# ZULU-T868-TX-Prototype.net
KiCad netlist of a schematic drawn in EAGLE
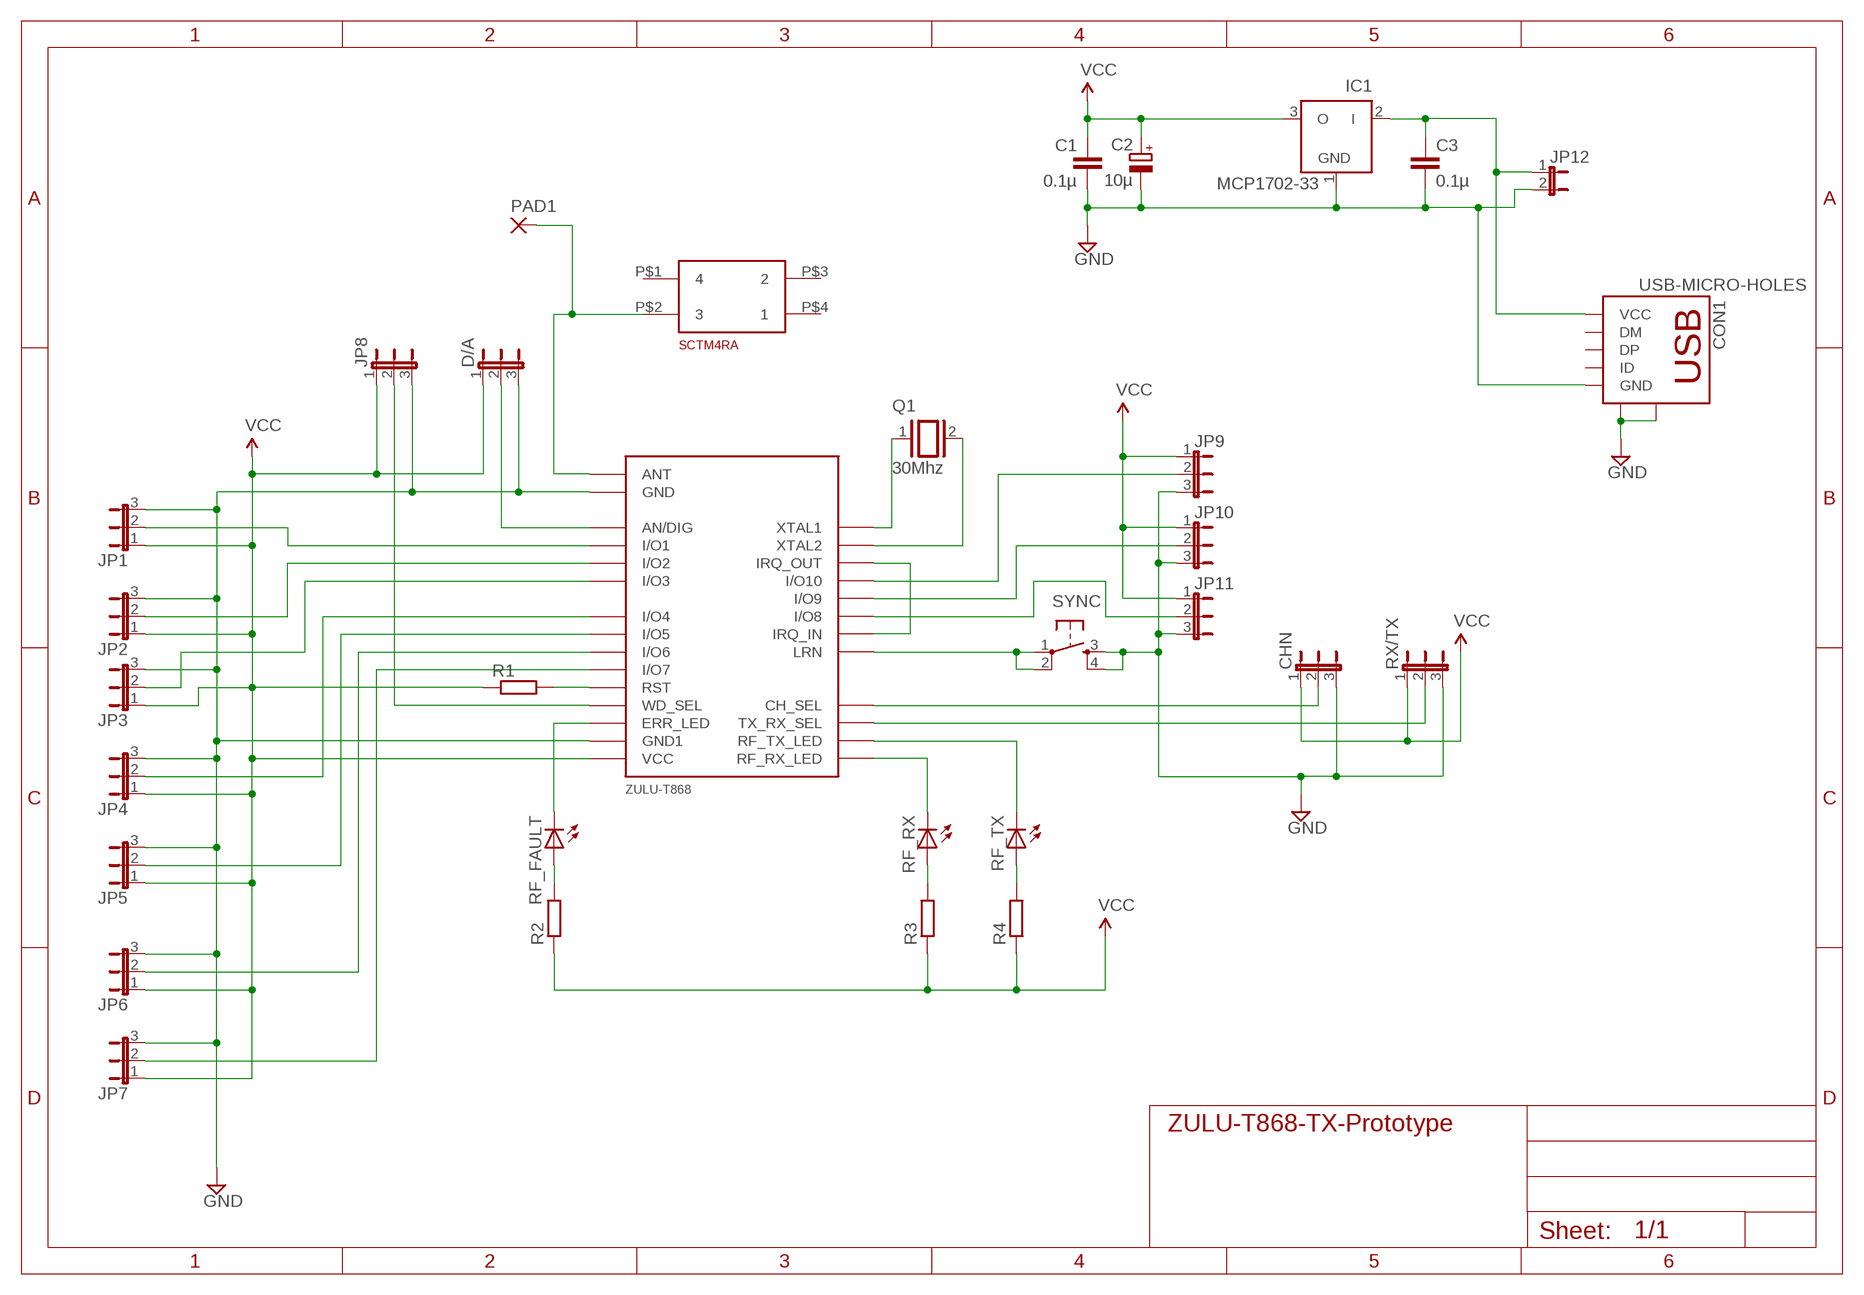
[diagram p0: schematic, sheet 1]

(export (version "E")
  (design (tool "Eeschema 10.0.6"))
  (components
    (comp (ref "C1")
      (value "0.1µ")
      (footprint "eagle-import:C0805")
      (libsource (lib "eagle-import") (part "C-EUC0805"))
    )
    (comp (ref "C2")
      (value "10µ")
      (footprint "eagle-import:E1,8-4")
      (libsource (lib "eagle-import") (part "CPOL-EUE1.8-4"))
    )
    (comp (ref "C3")
      (value "0.1µ")
      (footprint "eagle-import:C0805")
      (libsource (lib "eagle-import") (part "C-EUC0805"))
    )
    (comp (ref "CHN")
      (value "JP2E")
      (footprint "eagle-import:JP2")
      (libsource (lib "eagle-import") (part "JP2E"))
    )
    (comp (ref "CON1")
      (value "USB-MICRO-HOLES")
      (footprint "eagle-import:MICRO-USB-B-HOLES")
      (libsource (lib "eagle-import") (part "USB-MICRO-HOLES"))
    )
    (comp (ref "D/A")
      (value "JP2E")
      (footprint "eagle-import:JP2")
      (libsource (lib "eagle-import") (part "JP2E"))
    )
    (comp (ref "IC1")
      (value "MCP1702-33")
      (footprint "eagle-import:TO92")
      (libsource (lib "eagle-import") (part "MCP1702Z"))
    )
    (comp (ref "JP1")
      (value "JP2E")
      (footprint "eagle-import:JP2")
      (libsource (lib "eagle-import") (part "JP2E"))
    )
    (comp (ref "JP2")
      (value "JP2E")
      (footprint "eagle-import:JP2")
      (libsource (lib "eagle-import") (part "JP2E"))
    )
    (comp (ref "JP3")
      (value "JP2E")
      (footprint "eagle-import:JP2")
      (libsource (lib "eagle-import") (part "JP2E"))
    )
    (comp (ref "JP4")
      (value "JP2E")
      (footprint "eagle-import:JP2")
      (libsource (lib "eagle-import") (part "JP2E"))
    )
    (comp (ref "JP5")
      (value "JP2E")
      (footprint "eagle-import:JP2")
      (libsource (lib "eagle-import") (part "JP2E"))
    )
    (comp (ref "JP6")
      (value "JP2E")
      (footprint "eagle-import:JP2")
      (libsource (lib "eagle-import") (part "JP2E"))
    )
    (comp (ref "JP7")
      (value "JP2E")
      (footprint "eagle-import:JP2")
      (libsource (lib "eagle-import") (part "JP2E"))
    )
    (comp (ref "JP8")
      (value "JP2E")
      (footprint "eagle-import:JP2")
      (libsource (lib "eagle-import") (part "JP2E"))
    )
    (comp (ref "JP9")
      (value "JP2E")
      (footprint "eagle-import:JP2")
      (libsource (lib "eagle-import") (part "JP2E"))
    )
    (comp (ref "JP10")
      (value "JP2E")
      (footprint "eagle-import:JP2")
      (libsource (lib "eagle-import") (part "JP2E"))
    )
    (comp (ref "JP11")
      (value "JP2E")
      (footprint "eagle-import:JP2")
      (libsource (lib "eagle-import") (part "JP2E"))
    )
    (comp (ref "JP12")
      (value "JP1E")
      (footprint "eagle-import:JP1")
      (libsource (lib "eagle-import") (part "JP1E"))
    )
    (comp (ref "PAD1")
      (value "1,6/0,8")
      (footprint "eagle-import:1,6_0,8")
      (libsource (lib "eagle-import") (part "1,6/0,8"))
    )
    (comp (ref "Q1")
      (value "30Mhz")
      (footprint "eagle-import:QS")
      (libsource (lib "eagle-import") (part "XTAL/S"))
    )
    (comp (ref "R1")
      (value "R-EU_M0805")
      (footprint "eagle-import:M0805")
      (libsource (lib "eagle-import") (part "R-EU_M0805"))
    )
    (comp (ref "R2")
      (value "R-EU_M0805")
      (footprint "eagle-import:M0805")
      (libsource (lib "eagle-import") (part "R-EU_M0805"))
    )
    (comp (ref "R3")
      (value "R-EU_M0805")
      (footprint "eagle-import:M0805")
      (libsource (lib "eagle-import") (part "R-EU_M0805"))
    )
    (comp (ref "R4")
      (value "R-EU_M0805")
      (footprint "eagle-import:M0805")
      (libsource (lib "eagle-import") (part "R-EU_M0805"))
    )
    (comp (ref "RF_FAULT")
      (value "LEDCHIPLED_0805")
      (footprint "eagle-import:CHIPLED_0805")
      (libsource (lib "eagle-import") (part "LEDCHIPLED_0805"))
    )
    (comp (ref "RF_RX")
      (value "LEDCHIPLED_0805")
      (footprint "eagle-import:CHIPLED_0805")
      (libsource (lib "eagle-import") (part "LEDCHIPLED_0805"))
    )
    (comp (ref "RF_TX")
      (value "LEDCHIPLED_0805")
      (footprint "eagle-import:CHIPLED_0805")
      (libsource (lib "eagle-import") (part "LEDCHIPLED_0805"))
    )
    (comp (ref "RX/TX")
      (value "JP2E")
      (footprint "eagle-import:JP2")
      (libsource (lib "eagle-import") (part "JP2E"))
    )
    (comp (ref "SYNC")
      (value "TAC_SWITCHPTH")
      (footprint "eagle-import:TACTILE-PTH")
      (libsource (lib "eagle-import") (part "TAC_SWITCHPTH"))
    )
    (comp (ref "U$1")
      (value "SCTM4RA")
      (footprint "eagle-import:SCTM4RA")
      (libsource (lib "eagle-import") (part "SCTM4RA"))
    )
    (comp (ref "U$2")
      (value "ZULU-T868")
      (footprint "eagle-import:ZULU-T-MODULE")
      (libsource (lib "eagle-import") (part "ZULU-T868"))
    )
  )
  (nets
    (net (code "1") (name "GND") (class "Default")
      (node (ref "C1") (pin "2") (pinfunction "2_2") (pintype "passive"))
      (node (ref "C2") (pin "-") (pinfunction "-_-") (pintype "passive"))
      (node (ref "C3") (pin "2") (pinfunction "2_2") (pintype "passive"))
      (node (ref "CHN") (pin "3") (pinfunction "3_3") (pintype "passive"))
      (node (ref "CON1") (pin "P$5") (pinfunction "GND_P$5") (pintype "bidirectional"))
      (node (ref "CON1") (pin "SHIELD1") (pinfunction "SHIELD1_SHIELD1") (pintype "bidirectional"))
      (node (ref "CON1") (pin "SHIELD2") (pinfunction "SHIELD2_SHIELD2") (pintype "bidirectional"))
      (node (ref "D/A") (pin "3") (pinfunction "3_3") (pintype "passive"))
      (node (ref "IC1") (pin "1") (pinfunction "GND_1") (pintype "power_in"))
      (node (ref "JP1") (pin "3") (pinfunction "3_3") (pintype "passive"))
      (node (ref "JP10") (pin "3") (pinfunction "3_3") (pintype "passive"))
      (node (ref "JP11") (pin "3") (pinfunction "3_3") (pintype "passive"))
      (node (ref "JP12") (pin "2") (pinfunction "2_2") (pintype "passive"))
      (node (ref "JP2") (pin "3") (pinfunction "3_3") (pintype "passive"))
      (node (ref "JP3") (pin "3") (pinfunction "3_3") (pintype "passive"))
      (node (ref "JP4") (pin "3") (pinfunction "3_3") (pintype "passive"))
      (node (ref "JP5") (pin "3") (pinfunction "3_3") (pintype "passive"))
      (node (ref "JP6") (pin "3") (pinfunction "3_3") (pintype "passive"))
      (node (ref "JP7") (pin "3") (pinfunction "3_3") (pintype "passive"))
      (node (ref "JP8") (pin "3") (pinfunction "3_3") (pintype "passive"))
      (node (ref "JP9") (pin "3") (pinfunction "3_3") (pintype "passive"))
      (node (ref "RX/TX") (pin "3") (pinfunction "3_3") (pintype "passive"))
      (node (ref "SYNC") (pin "3") (pinfunction "3_3") (pintype "passive"))
      (node (ref "SYNC") (pin "4") (pinfunction "4_4") (pintype "passive"))
      (node (ref "U$2") (pin "P$15") (pinfunction "GND1_P$15") (pintype "bidirectional"))
      (node (ref "U$2") (pin "P$2") (pinfunction "GND_P$2") (pintype "bidirectional"))
    )
    (net (code "2") (name "Net-(CON1-VCC)") (class "Default")
      (node (ref "C3") (pin "1") (pinfunction "1_1") (pintype "passive"))
      (node (ref "CON1") (pin "P$1") (pinfunction "VCC_P$1") (pintype "bidirectional"))
      (node (ref "IC1") (pin "2") (pinfunction "I_2") (pintype "input"))
      (node (ref "JP12") (pin "1") (pinfunction "1_1") (pintype "passive"))
    )
    (net (code "3") (name "Net-(PAD1-P)") (class "Default")
      (node (ref "PAD1") (pin "1") (pinfunction "P_1") (pintype "passive"))
      (node (ref "U$1") (pin "P$2") (pinfunction "3_P$2") (pintype "bidirectional"))
      (node (ref "U$2") (pin "P$1") (pinfunction "ANT_P$1") (pintype "bidirectional"))
    )
    (net (code "4") (name "Net-(R2-Pad2)") (class "Default")
      (node (ref "R2") (pin "2") (pinfunction "2_2") (pintype "passive"))
      (node (ref "RF_FAULT") (pin "A") (pinfunction "A_A") (pintype "passive"))
    )
    (net (code "5") (name "Net-(R3-Pad2)") (class "Default")
      (node (ref "R3") (pin "2") (pinfunction "2_2") (pintype "passive"))
      (node (ref "RF_RX") (pin "A") (pinfunction "A_A") (pintype "passive"))
    )
    (net (code "6") (name "Net-(R4-Pad2)") (class "Default")
      (node (ref "R4") (pin "2") (pinfunction "2_2") (pintype "passive"))
      (node (ref "RF_TX") (pin "A") (pinfunction "A_A") (pintype "passive"))
    )
    (net (code "7") (name "Net-(U$2-AN{slash}DIG)") (class "Default")
      (node (ref "D/A") (pin "2") (pinfunction "2_2") (pintype "passive"))
      (node (ref "U$2") (pin "P$3") (pinfunction "AN/DIG_P$3") (pintype "bidirectional"))
    )
    (net (code "8") (name "Net-(U$2-CH_SEL)") (class "Default")
      (node (ref "CHN") (pin "2") (pinfunction "2_2") (pintype "passive"))
      (node (ref "U$2") (pin "P$20") (pinfunction "CH_SEL_P$20") (pintype "bidirectional"))
    )
    (net (code "9") (name "Net-(U$2-ERR_LED)") (class "Default")
      (node (ref "RF_FAULT") (pin "C") (pinfunction "C_C") (pintype "passive"))
      (node (ref "U$2") (pin "P$14") (pinfunction "ERR_LED_P$14") (pintype "bidirectional"))
    )
    (net (code "10") (name "Net-(U$2-IRQ_IN)") (class "Default")
      (node (ref "U$2") (pin "P$24") (pinfunction "IRQ_IN_P$24") (pintype "bidirectional"))
      (node (ref "U$2") (pin "P$28") (pinfunction "IRQ_OUT_P$28") (pintype "bidirectional"))
    )
    (net (code "11") (name "Net-(U$2-I{slash}O1)") (class "Default")
      (node (ref "JP1") (pin "2") (pinfunction "2_2") (pintype "passive"))
      (node (ref "U$2") (pin "P$4") (pinfunction "I/O1_P$4") (pintype "bidirectional"))
    )
    (net (code "12") (name "Net-(U$2-I{slash}O2)") (class "Default")
      (node (ref "JP2") (pin "2") (pinfunction "2_2") (pintype "passive"))
      (node (ref "U$2") (pin "P$5") (pinfunction "I/O2_P$5") (pintype "bidirectional"))
    )
    (net (code "13") (name "Net-(U$2-I{slash}O3)") (class "Default")
      (node (ref "JP3") (pin "2") (pinfunction "2_2") (pintype "passive"))
      (node (ref "U$2") (pin "P$6") (pinfunction "I/O3_P$6") (pintype "bidirectional"))
    )
    (net (code "14") (name "Net-(U$2-I{slash}O4)") (class "Default")
      (node (ref "JP4") (pin "2") (pinfunction "2_2") (pintype "passive"))
      (node (ref "U$2") (pin "P$8") (pinfunction "I/O4_P$8") (pintype "bidirectional"))
    )
    (net (code "15") (name "Net-(U$2-I{slash}O5)") (class "Default")
      (node (ref "JP5") (pin "2") (pinfunction "2_2") (pintype "passive"))
      (node (ref "U$2") (pin "P$9") (pinfunction "I/O5_P$9") (pintype "bidirectional"))
    )
    (net (code "16") (name "Net-(U$2-I{slash}O6)") (class "Default")
      (node (ref "JP6") (pin "2") (pinfunction "2_2") (pintype "passive"))
      (node (ref "U$2") (pin "P$10") (pinfunction "I/O6_P$10") (pintype "bidirectional"))
    )
    (net (code "17") (name "Net-(U$2-I{slash}O7)") (class "Default")
      (node (ref "JP7") (pin "2") (pinfunction "2_2") (pintype "passive"))
      (node (ref "U$2") (pin "P$11") (pinfunction "I/O7_P$11") (pintype "bidirectional"))
    )
    (net (code "18") (name "Net-(U$2-I{slash}O8)") (class "Default")
      (node (ref "JP11") (pin "2") (pinfunction "2_2") (pintype "passive"))
      (node (ref "U$2") (pin "P$25") (pinfunction "I/O8_P$25") (pintype "bidirectional"))
    )
    (net (code "19") (name "Net-(U$2-I{slash}O9)") (class "Default")
      (node (ref "JP10") (pin "2") (pinfunction "2_2") (pintype "passive"))
      (node (ref "U$2") (pin "P$26") (pinfunction "I/O9_P$26") (pintype "bidirectional"))
    )
    (net (code "20") (name "Net-(U$2-I{slash}O10)") (class "Default")
      (node (ref "JP9") (pin "2") (pinfunction "2_2") (pintype "passive"))
      (node (ref "U$2") (pin "P$27") (pinfunction "I/O10_P$27") (pintype "bidirectional"))
    )
    (net (code "21") (name "Net-(U$2-LRN)") (class "Default")
      (node (ref "SYNC") (pin "1") (pinfunction "1_1") (pintype "passive"))
      (node (ref "SYNC") (pin "2") (pinfunction "2_2") (pintype "passive"))
      (node (ref "U$2") (pin "P$23") (pinfunction "LRN_P$23") (pintype "bidirectional"))
    )
    (net (code "22") (name "Net-(U$2-RF_RX_LED)") (class "Default")
      (node (ref "RF_RX") (pin "C") (pinfunction "C_C") (pintype "passive"))
      (node (ref "U$2") (pin "P$17") (pinfunction "RF_RX_LED_P$17") (pintype "bidirectional"))
    )
    (net (code "23") (name "Net-(U$2-RF_TX_LED)") (class "Default")
      (node (ref "RF_TX") (pin "C") (pinfunction "C_C") (pintype "passive"))
      (node (ref "U$2") (pin "P$18") (pinfunction "RF_TX_LED_P$18") (pintype "bidirectional"))
    )
    (net (code "24") (name "Net-(U$2-RST)") (class "Default")
      (node (ref "R1") (pin "2") (pinfunction "2_2") (pintype "passive"))
      (node (ref "U$2") (pin "P$12") (pinfunction "RST_P$12") (pintype "bidirectional"))
    )
    (net (code "25") (name "Net-(U$2-TX_RX_SEL)") (class "Default")
      (node (ref "RX/TX") (pin "2") (pinfunction "2_2") (pintype "passive"))
      (node (ref "U$2") (pin "P$19") (pinfunction "TX_RX_SEL_P$19") (pintype "bidirectional"))
    )
    (net (code "26") (name "Net-(U$2-WD_SEL)") (class "Default")
      (node (ref "JP8") (pin "2") (pinfunction "2_2") (pintype "passive"))
      (node (ref "U$2") (pin "P$13") (pinfunction "WD_SEL_P$13") (pintype "bidirectional"))
    )
    (net (code "27") (name "Net-(U$2-XTAL1)") (class "Default")
      (node (ref "Q1") (pin "1") (pinfunction "1_1") (pintype "passive"))
      (node (ref "U$2") (pin "P$30") (pinfunction "XTAL1_P$30") (pintype "bidirectional"))
    )
    (net (code "28") (name "Net-(U$2-XTAL2)") (class "Default")
      (node (ref "Q1") (pin "2") (pinfunction "2_2") (pintype "passive"))
      (node (ref "U$2") (pin "P$29") (pinfunction "XTAL2_P$29") (pintype "bidirectional"))
    )
    (net (code "29") (name "VCC") (class "Default")
      (node (ref "C1") (pin "1") (pinfunction "1_1") (pintype "passive"))
      (node (ref "C2") (pin "+") (pinfunction "+_+") (pintype "passive"))
      (node (ref "CHN") (pin "1") (pinfunction "1_1") (pintype "passive"))
      (node (ref "D/A") (pin "1") (pinfunction "1_1") (pintype "passive"))
      (node (ref "IC1") (pin "3") (pinfunction "O_3") (pintype "input"))
      (node (ref "JP1") (pin "1") (pinfunction "1_1") (pintype "passive"))
      (node (ref "JP10") (pin "1") (pinfunction "1_1") (pintype "passive"))
      (node (ref "JP11") (pin "1") (pinfunction "1_1") (pintype "passive"))
      (node (ref "JP2") (pin "1") (pinfunction "1_1") (pintype "passive"))
      (node (ref "JP3") (pin "1") (pinfunction "1_1") (pintype "passive"))
      (node (ref "JP4") (pin "1") (pinfunction "1_1") (pintype "passive"))
      (node (ref "JP5") (pin "1") (pinfunction "1_1") (pintype "passive"))
      (node (ref "JP6") (pin "1") (pinfunction "1_1") (pintype "passive"))
      (node (ref "JP7") (pin "1") (pinfunction "1_1") (pintype "passive"))
      (node (ref "JP8") (pin "1") (pinfunction "1_1") (pintype "passive"))
      (node (ref "JP9") (pin "1") (pinfunction "1_1") (pintype "passive"))
      (node (ref "R1") (pin "1") (pinfunction "1_1") (pintype "passive"))
      (node (ref "R2") (pin "1") (pinfunction "1_1") (pintype "passive"))
      (node (ref "R3") (pin "1") (pinfunction "1_1") (pintype "passive"))
      (node (ref "R4") (pin "1") (pinfunction "1_1") (pintype "passive"))
      (node (ref "RX/TX") (pin "1") (pinfunction "1_1") (pintype "passive"))
      (node (ref "U$2") (pin "P$16") (pinfunction "VCC_P$16") (pintype "bidirectional"))
    )
    (net (code "30") (name "unconnected-(CON1-DM-PadP$2)") (class "Default")
      (node (ref "CON1") (pin "P$2") (pinfunction "DM_P$2") (pintype "bidirectional"))
    )
    (net (code "31") (name "unconnected-(CON1-DP-PadP$3)") (class "Default")
      (node (ref "CON1") (pin "P$3") (pinfunction "DP_P$3") (pintype "bidirectional"))
    )
    (net (code "32") (name "unconnected-(CON1-ID-PadP$4)") (class "Default")
      (node (ref "CON1") (pin "P$4") (pinfunction "ID_P$4") (pintype "bidirectional"))
    )
    (net (code "33") (name "unconnected-(U$1-1-PadP$4)") (class "Default")
      (node (ref "U$1") (pin "P$4") (pinfunction "1_P$4") (pintype "bidirectional"))
    )
    (net (code "34") (name "unconnected-(U$1-2-PadP$3)") (class "Default")
      (node (ref "U$1") (pin "P$3") (pinfunction "2_P$3") (pintype "bidirectional"))
    )
    (net (code "35") (name "unconnected-(U$1-4-PadP$1)") (class "Default")
      (node (ref "U$1") (pin "P$1") (pinfunction "4_P$1") (pintype "bidirectional"))
    )
  )
)
